# Battery_Charger.net
KiCad netlist of a schematic drawn in Altium Designer
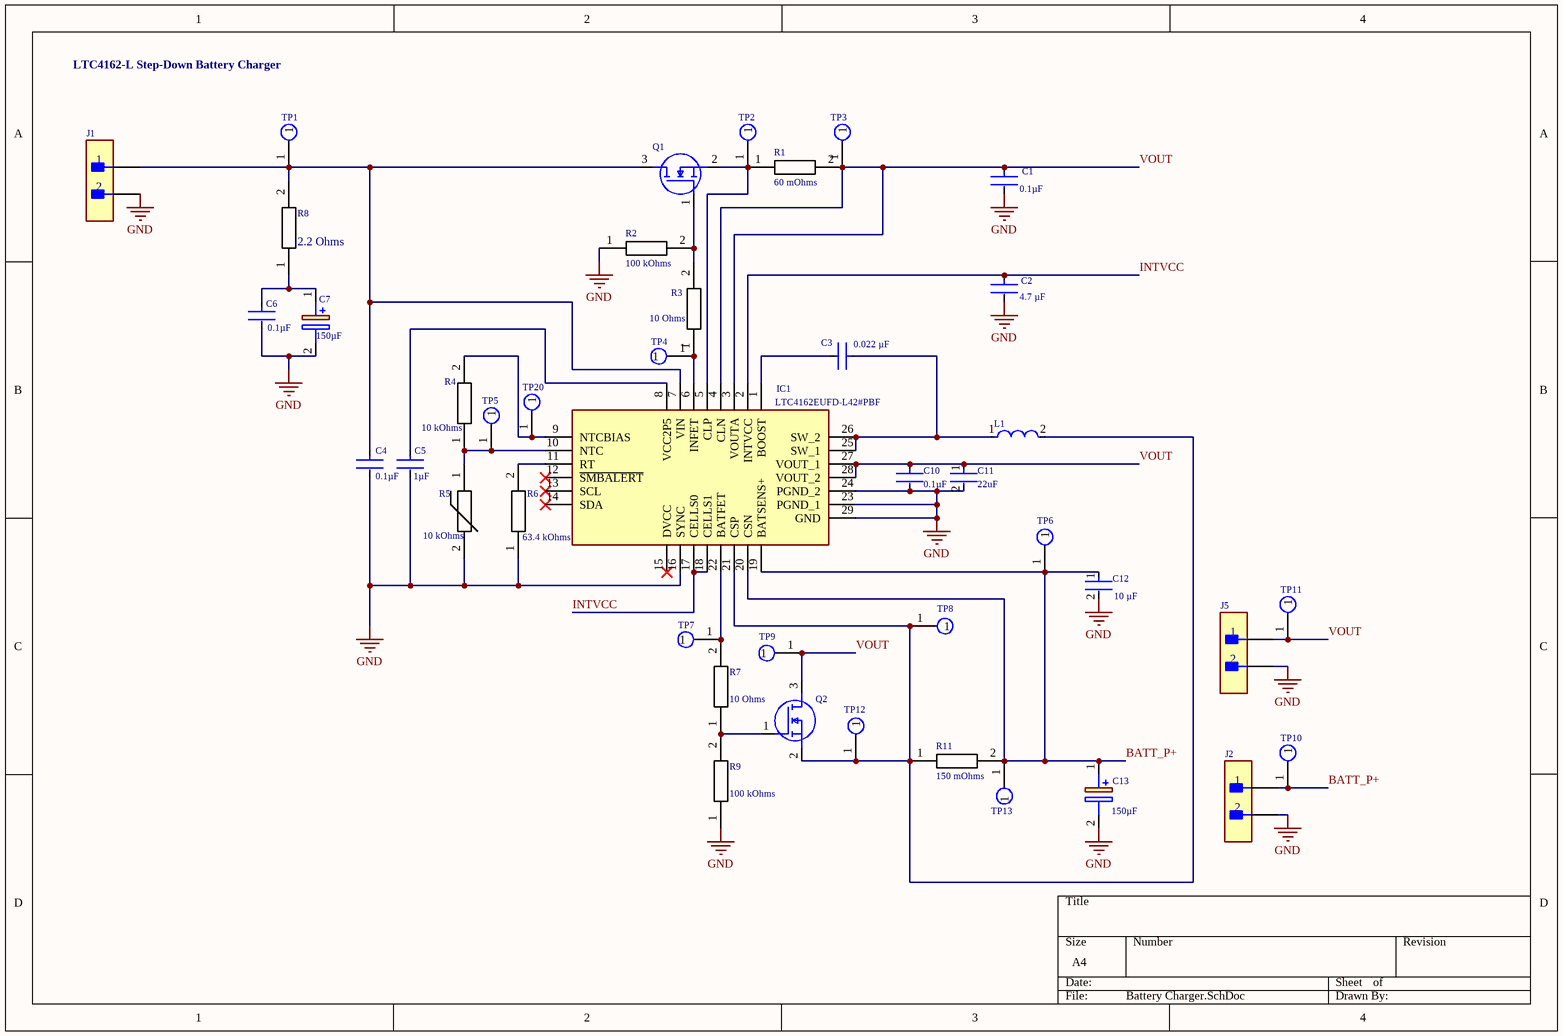
[diagram p0: Battery Charger.SchDoc]

(export (version "E")
  (design (tool "Eeschema 10.0.6"))
  (components
    (comp (ref "C1")
      (value "0.1µF")
      (footprint "FP-CC0603-DA-MFG")
      (description "CAP CER 0.1UF 16V X7R 0603 CC0603KRX7R7BB104")
      (fields
        (field (name "OCTOPART") "https://octopart.com/cc0603krx7r7bb104-yageo-192941")
        (field (name "TOLERANCE") "0.1")
      )
      (libsource (lib "Altium Content Vault") (part "11868f565c42a9108669ba33697ecf6"))
    )
    (comp (ref "C2")
      (value "4.7 µF")
      (footprint "FP-CC0603-DA-MFG")
      (description "CAP CER 4.7UF 10V X5R 0603 CC0603KRX5R6BB475")
      (fields (field (name "MANUFACTURER PART NUMBER") "CC0603KRX5R6BB475") (field (name "VOLTAGE") "10 V"))
      (libsource (lib "Altium Content Vault") (part "11868f565c42a9108669ba33697ecf6"))
    )
    (comp (ref "C3")
      (value "0.022 µF")
      (footprint "FP-C0603C-CF-MFG")
      (description "Ceramic Capacitor 0.022Uf 16V, X7R, 10%, 0603, Full Reel C0603C223K4RACTU")
      (fields
        (field (name "OCTOPART") "https://octopart.com/c0603c223k4ractu-kemet-123286")
        (field (name "MANUFACTURER PART NUMBER") "C0603C223K4RACTU")
      )
      (libsource (lib "Altium Content Vault") (part "b4654b650e69147ec39a6b967a45e02"))
    )
    (comp (ref "C4")
      (value "0.1µF")
      (footprint "FP-CC0603-DA-MFG")
      (description "CAP CER 0.1UF 16V X7R 0603 CC0603KRX7R7BB104")
      (fields
        (field (name "OCTOPART") "https://octopart.com/cc0603krx7r7bb104-yageo-192941")
        (field (name "TOLERANCE") "0.1")
      )
      (libsource (lib "Altium Content Vault") (part "11868f565c42a9108669ba33697ecf6"))
    )
    (comp (ref "C5")
      (value "1µF")
      (footprint "FP-CC0603-DA-MFG")
      (description "CAP CER 1UF 25V X5R 0603 CC0603KRX5R8BB105")
      (fields
        (field (name "OCTOPART") "https://octopart.com/cc0603krx5r8bb105-yageo-9292811")
        (field (name "MANUFACTURER") "YAGEO")
      )
      (libsource (lib "Altium Content Vault") (part "11868f565c42a9108669ba33697ecf6"))
    )
    (comp (ref "C6")
      (value "0.1µF")
      (footprint "FP-CC0603-DA-MFG")
      (description "CAP CER 0.1UF 16V X7R 0603 CC0603KRX7R7BB104")
      (fields
        (field (name "OCTOPART") "https://octopart.com/cc0603krx7r7bb104-yageo-192941")
        (field (name "TOLERANCE") "0.1")
      )
      (libsource (lib "Altium Content Vault") (part "11868f565c42a9108669ba33697ecf6"))
    )
    (comp (ref "C7")
      (value "150µF")
      (footprint "SamacSys:CAPAE660X730N")
      (description "Capacitor Polarised A765EG157M1CLAE027")
      (fields
        (field (name "MANUFACTURER_PART_NUMBER") "A765EG157M1CLAE027")
        (field (name "MOUSER PART NUMBER") "80-A765EG157M1CLAE27")
      )
      (libsource (lib "*") (part "A765EG157M1CLAE027"))
    )
    (comp (ref "C10")
      (value "0.1µF")
      (footprint "FP-CC0603-DA-MFG")
      (description "CAP CER 0.1UF 16V X7R 0603 CC0603KRX7R7BB104")
      (fields
        (field (name "OCTOPART") "https://octopart.com/cc0603krx7r7bb104-yageo-192941")
        (field (name "TOLERANCE") "0.1")
      )
      (libsource (lib "Altium Content Vault") (part "11868f565c42a9108669ba33697ecf6"))
    )
    (comp (ref "C11")
      (value "22uF")
      (footprint "FP-GRM31C-0_2-e0_3_0_8-MFG")
      (fields (field (name "VOLTAGE") "10V") (field (name "TOLERANCE") "10%"))
      (libsource (lib "Altium Content Vault") (part "02cd4be3c70576c341d710602a673aa"))
    )
    (comp (ref "C12")
      (value "10 µF")
      (footprint "1206")
      (description "CC1206KKX5R7BB106 10 µF ±10% 16V Ceramic Capacitor X5R 1206 (3216 Metric)")
      (fields
        (field (name "OCTOPART") "https://octopart.com/c0603c223k4ractu-kemet-123286")
        (field (name "MANUFACTURER PART NUMBER") "C0603C223K4RACTU")
      )
      (libsource (lib "Capacitors") (part "CC1206KKX5R7BB106"))
    )
    (comp (ref "C13")
      (value "150µF")
      (footprint "SamacSys:CAPAE660X730N")
      (description "Capacitor Polarised A765EG157M1CLAE027")
      (fields
        (field (name "MANUFACTURER_PART_NUMBER") "A765EG157M1CLAE027")
        (field (name "MOUSER PART NUMBER") "80-A765EG157M1CLAE27")
      )
      (libsource (lib "*") (part "A765EG157M1CLAE027"))
    )
    (comp (ref "IC1")
      (value "LTC4162EUFD-L42#PBF")
      (footprint "SamacSys:QFN50P400X500X80-29N-D")
      (description "Integrated Circuit")
      (fields (field (name "MOUSER PART NUMBER") "584-4162EUFDL42PB"))
      (libsource (lib "SamacSys") (part "LTC4162EUFD-L42#PBF"))
    )
    (comp (ref "J1")
      (value "B2B-XH-A(LF)(SN)")
      (footprint "FP-B2B-XH-A_LF_SN-MFG")
      (description "CONN HEADER VERT 2POS 2.5MM")
      (libsource (lib "Altium Content Vault") (part "3bc925449376181038e59eaffc5286c"))
    )
    (comp (ref "J2")
      (value "B2B-XH-A(LF)(SN)")
      (footprint "FP-B2B-XH-A_LF_SN-MFG")
      (description "CONN HEADER VERT 2POS 2.5MM")
      (libsource (lib "Altium Content Vault") (part "3bc925449376181038e59eaffc5286c"))
    )
    (comp (ref "J5")
      (value "B2B-XH-A(LF)(SN)")
      (footprint "FP-B2B-XH-A_LF_SN-MFG")
      (description "CONN HEADER VERT 2POS 2.5MM")
      (libsource (lib "Altium Content Vault") (part "3bc925449376181038e59eaffc5286c"))
    )
    (comp (ref "L1")
      (value "MLZ2012M1R0HT000")
      (footprint "FP-MLZ2012-1_25-MFG")
      (description "Shielded Multilayer Inductor 1uH ±20% 800mA 130mΩ SMD 0805")
      (fields (field (name "TOLERANCE") "20%"))
      (libsource (lib "Altium Content Vault") (part "725321dda6339637d4d059423bc1c3c"))
    )
    (comp (ref "Q1")
      (value "IRLML6344TRPBF")
      (footprint "SamacSys:SOT95P237X112-3N")
      (description "MOSFET (N-Channel)")
      (fields (field (name "MOUSER PART NUMBER") "942-IRLML6344TRPBF"))
      (libsource (lib "SamacSys") (part "IRLML6344TRPBF"))
    )
    (comp (ref "Q2")
      (value "IRLML6344TRPBF")
      (footprint "SamacSys:SOT95P237X112-3N")
      (description "MOSFET (N-Channel)")
      (fields (field (name "MOUSER PART NUMBER") "942-IRLML6344TRPBF"))
      (libsource (lib "SamacSys") (part "IRLML6344TRPBF"))
    )
    (comp (ref "R1")
      (value "60 mOhms")
      (footprint "1206")
      (libsource (lib "resistors") (part "PE1206FRM070R06L Resistor"))
    )
    (comp (ref "R2")
      (value "100 kOhms")
      (footprint "RC0603FR-07100KL Resistor")
      (description "100 kOhms ±1% 0.1W, 1/10W Chip Resistor 0603 (1608 Metric) Moisture Resistant Thick Film")
      (libsource (lib "resistors") (part "RC0603FR-07100KL Resistor"))
    )
    (comp (ref "R3")
      (value "10 Ohms")
      (footprint "RC0603FR-0710RL Resistor")
      (description "10 Ohms ±1% 0.1W, 1/10W Chip Resistor 0603 (1608 Metric) Moisture Resistant Thick Film")
      (libsource (lib "resistors") (part "RC0603FR-0710RL Resistor"))
    )
    (comp (ref "R4")
      (value "10 kOhms")
      (footprint "RC0603FR-0710KL")
      (description "10 kOhms ±1% 0.1W, 1/10W Chip Resistor 0603 (1608 Metric) Moisture Resistant Thick Film")
      (libsource (lib "resistors") (part "RC0603FR-0710KL Resistor"))
    )
    (comp (ref "R5")
      (value "10 kOhms")
      (footprint "NCP18XH103F03RB")
      (description "THERMISTOR NTC 10KOHM 3380K 0603")
      (libsource (lib "resistors") (part "NCP18XH103F03RB Resistor"))
    )
    (comp (ref "R6")
      (value "63.4 kOhms")
      (footprint "SamacSys:RESC1608X55N")
      (description "RC0603FR-0763K4L")
      (fields (field (name "MOUSER PART NUMBER") "603-RC0603FR-0763K4L"))
      (libsource (lib "*") (part "RC0603FR-0763K4L"))
    )
    (comp (ref "R7")
      (value "10 Ohms")
      (footprint "RC0603FR-0710RL Resistor")
      (description "10 Ohms ±1% 0.1W, 1/10W Chip Resistor 0603 (1608 Metric) Moisture Resistant Thick Film")
      (libsource (lib "resistors") (part "RC0603FR-0710RL Resistor"))
    )
    (comp (ref "R8")
      (value "2.2 Ohms")
      (footprint "1206")
      (libsource (lib "resistors") (part "SR1206FR-7T2R2L Resistor"))
    )
    (comp (ref "R9")
      (value "100 kOhms")
      (footprint "RC0603FR-07100KL Resistor")
      (description "100 kOhms ±1% 0.1W, 1/10W Chip Resistor 0603 (1608 Metric) Moisture Resistant Thick Film")
      (libsource (lib "resistors") (part "RC0603FR-07100KL Resistor"))
    )
    (comp (ref "R11")
      (value "150 mOhms")
      (footprint "1206")
      (libsource (lib "resistors") (part "WSL1206R1500FEA Resistor"))
    )
    (comp (ref "TP1")
      (value "S2761-46R")
      (footprint "SamacSys:S276146R")
      (description "Test Point")
      (fields (field (name "MOUSER PART NUMBER") "855-S2761-46R"))
      (libsource (lib "SamacSys") (part "S2761-46R"))
    )
    (comp (ref "TP2")
      (value "S2761-46R")
      (footprint "SamacSys:S276146R")
      (description "Test Point")
      (fields (field (name "MOUSER PART NUMBER") "855-S2761-46R"))
      (libsource (lib "SamacSys") (part "S2761-46R"))
    )
    (comp (ref "TP3")
      (value "S2761-46R")
      (footprint "SamacSys:S276146R")
      (description "Test Point")
      (fields (field (name "MOUSER PART NUMBER") "855-S2761-46R"))
      (libsource (lib "SamacSys") (part "S2761-46R"))
    )
    (comp (ref "TP4")
      (value "S2761-46R")
      (footprint "SamacSys:S276146R")
      (description "Test Point")
      (fields (field (name "MOUSER PART NUMBER") "855-S2761-46R"))
      (libsource (lib "SamacSys") (part "S2761-46R"))
    )
    (comp (ref "TP5")
      (value "S2761-46R")
      (footprint "SamacSys:S276146R")
      (description "Test Point")
      (fields (field (name "MOUSER PART NUMBER") "855-S2761-46R"))
      (libsource (lib "SamacSys") (part "S2761-46R"))
    )
    (comp (ref "TP6")
      (value "S2761-46R")
      (footprint "SamacSys:S276146R")
      (description "Test Point")
      (fields (field (name "MOUSER PART NUMBER") "855-S2761-46R"))
      (libsource (lib "SamacSys") (part "S2761-46R"))
    )
    (comp (ref "TP7")
      (value "S2761-46R")
      (footprint "SamacSys:S276146R")
      (description "Test Point")
      (fields (field (name "MOUSER PART NUMBER") "855-S2761-46R"))
      (libsource (lib "SamacSys") (part "S2761-46R"))
    )
    (comp (ref "TP8")
      (value "S2761-46R")
      (footprint "SamacSys:S276146R")
      (description "Test Point")
      (fields (field (name "MOUSER PART NUMBER") "855-S2761-46R"))
      (libsource (lib "SamacSys") (part "S2761-46R"))
    )
    (comp (ref "TP9")
      (value "S2761-46R")
      (footprint "SamacSys:S276146R")
      (description "Test Point")
      (fields (field (name "MOUSER PART NUMBER") "855-S2761-46R"))
      (libsource (lib "SamacSys") (part "S2761-46R"))
    )
    (comp (ref "TP10")
      (value "S2761-46R")
      (footprint "SamacSys:S276146R")
      (description "Test Point")
      (fields (field (name "MOUSER PART NUMBER") "855-S2761-46R"))
      (libsource (lib "SamacSys") (part "S2761-46R"))
    )
    (comp (ref "TP11")
      (value "S2761-46R")
      (footprint "SamacSys:S276146R")
      (description "Test Point")
      (fields (field (name "MOUSER PART NUMBER") "855-S2761-46R"))
      (libsource (lib "SamacSys") (part "S2761-46R"))
    )
    (comp (ref "TP12")
      (value "S2761-46R")
      (footprint "SamacSys:S276146R")
      (description "Test Point")
      (fields (field (name "MOUSER PART NUMBER") "855-S2761-46R"))
      (libsource (lib "SamacSys") (part "S2761-46R"))
    )
    (comp (ref "TP13")
      (value "S2761-46R")
      (footprint "SamacSys:S276146R")
      (description "Test Point")
      (fields (field (name "MOUSER PART NUMBER") "855-S2761-46R"))
      (libsource (lib "SamacSys") (part "S2761-46R"))
    )
    (comp (ref "TP20")
      (value "S2761-46R")
      (footprint "SamacSys:S276146R")
      (description "Test Point")
      (fields (field (name "MOUSER PART NUMBER") "855-S2761-46R"))
      (libsource (lib "SamacSys") (part "S2761-46R"))
    )
  )
  (nets
    (net (code "1") (name "/BATT_P+") (class "Default")
      (node (ref "C12") (pin "1") (pinfunction "1_1") (pintype "passive"))
      (node (ref "C13") (pin "1") (pinfunction "+_1") (pintype "passive"))
      (node (ref "IC1") (pin "19") (pinfunction "BATSENS+_19") (pintype "passive"))
      (node (ref "IC1") (pin "20") (pinfunction "CSN_20") (pintype "passive"))
      (node (ref "J2") (pin "1") (pinfunction "1_1") (pintype "passive"))
      (node (ref "R11") (pin "2") (pinfunction "2_2") (pintype "passive"))
      (node (ref "TP10") (pin "1") (pinfunction "1_1") (pintype "passive"))
      (node (ref "TP13") (pin "1") (pinfunction "1_1") (pintype "passive"))
      (node (ref "TP6") (pin "1") (pinfunction "1_1") (pintype "passive"))
    )
    (net (code "2") (name "/INTVCC") (class "Default")
      (node (ref "C2") (pin "1") (pinfunction "1_1") (pintype "passive"))
      (node (ref "IC1") (pin "17") (pinfunction "CELLS0_17") (pintype "passive"))
      (node (ref "IC1") (pin "18") (pinfunction "CELLS1_18") (pintype "passive"))
      (node (ref "IC1") (pin "2") (pinfunction "INTVCC_2") (pintype "passive"))
    )
    (net (code "3") (name "/VOUT") (class "Default")
      (node (ref "C1") (pin "1") (pinfunction "1_1") (pintype "passive"))
      (node (ref "C10") (pin "1") (pinfunction "1_1") (pintype "passive"))
      (node (ref "C11") (pin "1") (pinfunction "1_1") (pintype "passive"))
      (node (ref "IC1") (pin "27") (pinfunction "VOUT_1_27") (pintype "passive"))
      (node (ref "IC1") (pin "28") (pinfunction "VOUT_2_28") (pintype "passive"))
      (node (ref "IC1") (pin "3") (pinfunction "VOUTA_3") (pintype "passive"))
      (node (ref "IC1") (pin "4") (pinfunction "CLN_4") (pintype "passive"))
      (node (ref "J5") (pin "1") (pinfunction "1_1") (pintype "passive"))
      (node (ref "Q2") (pin "3") (pinfunction "D_3") (pintype "passive"))
      (node (ref "R1") (pin "2") (pinfunction "2_2") (pintype "passive"))
      (node (ref "TP11") (pin "1") (pinfunction "1_1") (pintype "passive"))
      (node (ref "TP3") (pin "1") (pinfunction "1_1") (pintype "passive"))
      (node (ref "TP9") (pin "1") (pinfunction "1_1") (pintype "passive"))
    )
    (net (code "4") (name "GND") (class "Default")
      (node (ref "C1") (pin "2") (pinfunction "2_2") (pintype "passive"))
      (node (ref "C10") (pin "2") (pinfunction "2_2") (pintype "passive"))
      (node (ref "C11") (pin "2") (pinfunction "2_2") (pintype "passive"))
      (node (ref "C12") (pin "2") (pinfunction "2_2") (pintype "passive"))
      (node (ref "C13") (pin "2") (pinfunction "-_2") (pintype "passive"))
      (node (ref "C2") (pin "2") (pinfunction "2_2") (pintype "passive"))
      (node (ref "C4") (pin "2") (pinfunction "2_2") (pintype "passive"))
      (node (ref "C5") (pin "2") (pinfunction "2_2") (pintype "passive"))
      (node (ref "C6") (pin "2") (pinfunction "2_2") (pintype "passive"))
      (node (ref "C7") (pin "2") (pinfunction "-_2") (pintype "passive"))
      (node (ref "IC1") (pin "16") (pinfunction "SYNC_16") (pintype "passive"))
      (node (ref "IC1") (pin "23") (pinfunction "PGND_1_23") (pintype "passive"))
      (node (ref "IC1") (pin "24") (pinfunction "PGND_2_24") (pintype "passive"))
      (node (ref "IC1") (pin "29") (pinfunction "GND_29") (pintype "passive"))
      (node (ref "J1") (pin "2") (pinfunction "2_2") (pintype "passive"))
      (node (ref "J2") (pin "2") (pinfunction "2_2") (pintype "passive"))
      (node (ref "J5") (pin "2") (pinfunction "2_2") (pintype "passive"))
      (node (ref "R2") (pin "1") (pinfunction "1_1") (pintype "passive"))
      (node (ref "R5") (pin "2") (pinfunction "2_2") (pintype "passive"))
      (node (ref "R6") (pin "1") (pinfunction "1_1") (pintype "passive"))
      (node (ref "R9") (pin "1") (pinfunction "1_1") (pintype "passive"))
    )
    (net (code "5") (name "Net-(C7-+)") (class "Default")
      (node (ref "C6") (pin "1") (pinfunction "1_1") (pintype "passive"))
      (node (ref "C7") (pin "1") (pinfunction "+_1") (pintype "passive"))
      (node (ref "R8") (pin "1") (pinfunction "1_1") (pintype "passive"))
    )
    (net (code "6") (name "Net-(IC1-BATFET)") (class "Default")
      (node (ref "IC1") (pin "22") (pinfunction "BATFET_22") (pintype "passive"))
      (node (ref "R7") (pin "2") (pinfunction "2_2") (pintype "passive"))
      (node (ref "TP7") (pin "1") (pinfunction "1_1") (pintype "passive"))
    )
    (net (code "7") (name "Net-(IC1-BOOST)") (class "Default")
      (node (ref "C3") (pin "2") (pinfunction "2_2") (pintype "passive"))
      (node (ref "IC1") (pin "1") (pinfunction "BOOST_1") (pintype "passive"))
    )
    (net (code "8") (name "Net-(IC1-CLP)") (class "Default")
      (node (ref "IC1") (pin "5") (pinfunction "CLP_5") (pintype "passive"))
      (node (ref "Q1") (pin "2") (pinfunction "S_2") (pintype "passive"))
      (node (ref "R1") (pin "1") (pinfunction "1_1") (pintype "passive"))
      (node (ref "TP2") (pin "1") (pinfunction "1_1") (pintype "passive"))
    )
    (net (code "9") (name "Net-(IC1-CSP)") (class "Default")
      (node (ref "IC1") (pin "21") (pinfunction "CSP_21") (pintype "passive"))
      (node (ref "L1") (pin "2") (pinfunction "2_2") (pintype "passive"))
      (node (ref "Q2") (pin "2") (pinfunction "S_2") (pintype "passive"))
      (node (ref "R11") (pin "1") (pinfunction "1_1") (pintype "passive"))
      (node (ref "TP12") (pin "1") (pinfunction "1_1") (pintype "passive"))
      (node (ref "TP8") (pin "1") (pinfunction "1_1") (pintype "passive"))
    )
    (net (code "10") (name "Net-(IC1-INFET)") (class "Default")
      (node (ref "IC1") (pin "6") (pinfunction "INFET_6") (pintype "passive"))
      (node (ref "R3") (pin "1") (pinfunction "1_1") (pintype "passive"))
      (node (ref "TP4") (pin "1") (pinfunction "1_1") (pintype "passive"))
    )
    (net (code "11") (name "Net-(IC1-NTC)") (class "Default")
      (node (ref "IC1") (pin "10") (pinfunction "NTC_10") (pintype "passive"))
      (node (ref "R4") (pin "1") (pinfunction "1_1") (pintype "passive"))
      (node (ref "R5") (pin "1") (pinfunction "1_1") (pintype "passive"))
      (node (ref "TP5") (pin "1") (pinfunction "1_1") (pintype "passive"))
    )
    (net (code "12") (name "Net-(IC1-NTCBIAS)") (class "Default")
      (node (ref "IC1") (pin "9") (pinfunction "NTCBIAS_9") (pintype "passive"))
      (node (ref "R4") (pin "2") (pinfunction "2_2") (pintype "passive"))
      (node (ref "TP20") (pin "1") (pinfunction "1_1") (pintype "passive"))
    )
    (net (code "13") (name "Net-(IC1-RT)") (class "Default")
      (node (ref "IC1") (pin "11") (pinfunction "RT_11") (pintype "passive"))
      (node (ref "R6") (pin "2") (pinfunction "2_2") (pintype "passive"))
    )
    (net (code "14") (name "Net-(IC1-SW_1)") (class "Default")
      (node (ref "C3") (pin "1") (pinfunction "1_1") (pintype "passive"))
      (node (ref "IC1") (pin "25") (pinfunction "SW_1_25") (pintype "passive"))
      (node (ref "IC1") (pin "26") (pinfunction "SW_2_26") (pintype "passive"))
      (node (ref "L1") (pin "1") (pinfunction "1_1") (pintype "passive"))
    )
    (net (code "15") (name "Net-(IC1-VCC2P5)") (class "Default")
      (node (ref "C5") (pin "1") (pinfunction "1_1") (pintype "passive"))
      (node (ref "IC1") (pin "8") (pinfunction "VCC2P5_8") (pintype "passive"))
    )
    (net (code "16") (name "Net-(IC1-VIN)") (class "Default")
      (node (ref "C4") (pin "1") (pinfunction "1_1") (pintype "passive"))
      (node (ref "IC1") (pin "7") (pinfunction "VIN_7") (pintype "passive"))
      (node (ref "J1") (pin "1") (pinfunction "1_1") (pintype "passive"))
      (node (ref "Q1") (pin "3") (pinfunction "D_3") (pintype "passive"))
      (node (ref "R8") (pin "2") (pinfunction "2_2") (pintype "passive"))
      (node (ref "TP1") (pin "1") (pinfunction "1_1") (pintype "passive"))
    )
    (net (code "17") (name "Net-(Q1-G)") (class "Default")
      (node (ref "Q1") (pin "1") (pinfunction "G_1") (pintype "passive"))
      (node (ref "R2") (pin "2") (pinfunction "2_2") (pintype "passive"))
      (node (ref "R3") (pin "2") (pinfunction "2_2") (pintype "passive"))
    )
    (net (code "18") (name "Net-(Q2-G)") (class "Default")
      (node (ref "Q2") (pin "1") (pinfunction "G_1") (pintype "passive"))
      (node (ref "R7") (pin "1") (pinfunction "1_1") (pintype "passive"))
      (node (ref "R9") (pin "2") (pinfunction "2_2") (pintype "passive"))
    )
    (net (code "19") (name "unconnected-(IC1-DVCC-Pad15)") (class "Default")
      (node (ref "IC1") (pin "15") (pinfunction "DVCC_15") (pintype "passive+no_connect"))
    )
    (net (code "20") (name "unconnected-(IC1-SCL-Pad13)") (class "Default")
      (node (ref "IC1") (pin "13") (pinfunction "SCL_13") (pintype "passive+no_connect"))
    )
    (net (code "21") (name "unconnected-(IC1-SDA-Pad14)") (class "Default")
      (node (ref "IC1") (pin "14") (pinfunction "SDA_14") (pintype "passive+no_connect"))
    )
    (net (code "22") (name "unconnected-(IC1-~{SMBALERT}-Pad12)") (class "Default")
      (node (ref "IC1") (pin "12") (pinfunction "~{SMBALERT}_12") (pintype "passive+no_connect"))
    )
  )
)
